# MAAV_roomba.net
KiCad netlist of a schematic drawn in EAGLE
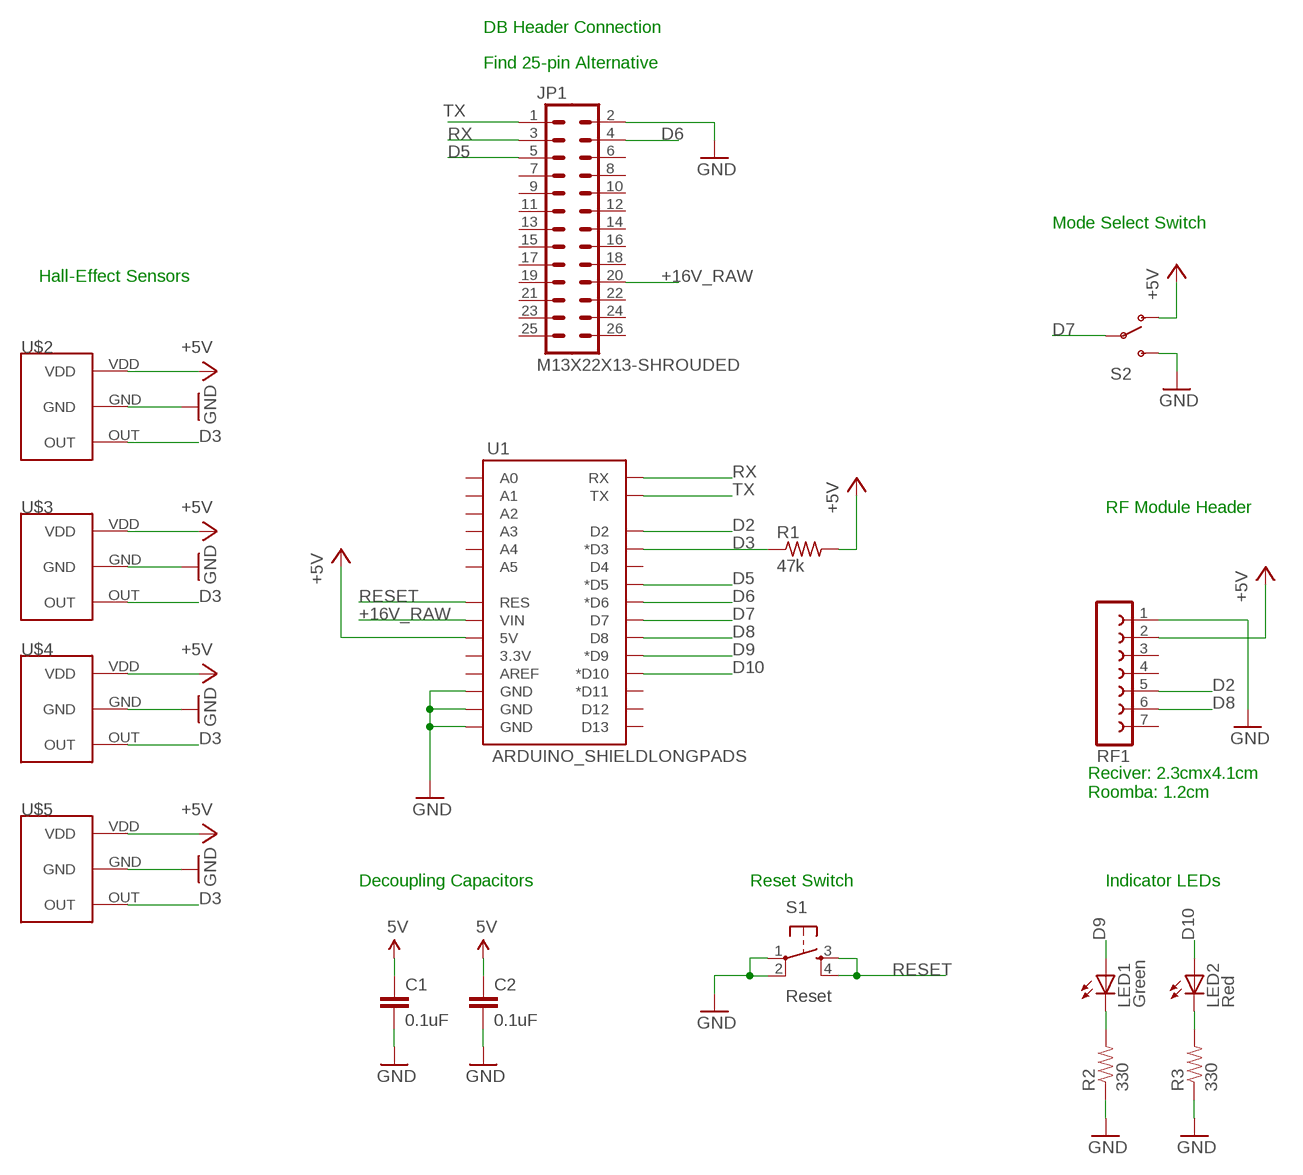
[diagram p0: schematic, sheet 1]

(export (version "E")
  (design (tool "Eeschema 10.0.6"))
  (components
    (comp (ref "C1")
      (value "0.1uF")
      (footprint "eagle-import:CAP-PTH-SMALL2")
      (libsource (lib "eagle-import") (part "CAPPTH2"))
    )
    (comp (ref "C2")
      (value "0.1uF")
      (footprint "eagle-import:CAP-PTH-SMALL2")
      (libsource (lib "eagle-import") (part "CAPPTH2"))
    )
    (comp (ref "JP1")
      (value "M13X22X13-SHROUDED")
      (footprint "eagle-import:2X25-SHROUDED")
      (libsource (lib "eagle-import") (part "M13X22X13-SHROUDED"))
    )
    (comp (ref "LED1")
      (value "Green")
      (footprint "eagle-import:LED5MM")
      (libsource (lib "eagle-import") (part "LED5MM"))
    )
    (comp (ref "LED2")
      (value "Red")
      (footprint "eagle-import:LED5MM")
      (libsource (lib "eagle-import") (part "LED5MM"))
    )
    (comp (ref "R1")
      (value "47k")
      (footprint "eagle-import:0309_10")
      (libsource (lib "eagle-import") (part "R-US_0309/10"))
    )
    (comp (ref "R2")
      (value "330")
      (footprint "eagle-import:AXIAL-0.4")
      (libsource (lib "eagle-import") (part "RESISTORPTH-1/4W"))
    )
    (comp (ref "R3")
      (value "330")
      (footprint "eagle-import:AXIAL-0.4")
      (libsource (lib "eagle-import") (part "RESISTORPTH-1/4W"))
    )
    (comp (ref "RF1")
      (value "FE07W")
      (footprint "eagle-import:FE07W")
      (libsource (lib "eagle-import") (part "FE07W"))
    )
    (comp (ref "S1")
      (value "Reset")
      (footprint "eagle-import:TACTILE-PTH")
      (libsource (lib "eagle-import") (part "TAC_SWITCHPTH"))
    )
    (comp (ref "S2")
      (value "SWITCH-SPDTPTH")
      (footprint "eagle-import:SWITCH-SPDT")
      (libsource (lib "eagle-import") (part "SWITCH-SPDTPTH"))
    )
    (comp (ref "U$2")
      (value "HALL_EFFECT")
      (footprint "eagle-import:HALL_EFFECT")
      (libsource (lib "eagle-import") (part "HALL_EFFECT"))
    )
    (comp (ref "U$3")
      (value "HALL_EFFECT")
      (footprint "eagle-import:HALL_EFFECT")
      (libsource (lib "eagle-import") (part "HALL_EFFECT"))
    )
    (comp (ref "U$4")
      (value "HALL_EFFECT")
      (footprint "eagle-import:HALL_EFFECT")
      (libsource (lib "eagle-import") (part "HALL_EFFECT"))
    )
    (comp (ref "U$5")
      (value "HALL_EFFECT")
      (footprint "eagle-import:HALL_EFFECT")
      (libsource (lib "eagle-import") (part "HALL_EFFECT"))
    )
    (comp (ref "U1")
      (value "ARDUINO_SHIELDLONGPADS")
      (footprint "eagle-import:DUEMILANOVE_SHIELD_LONGPADS")
      (libsource (lib "eagle-import") (part "ARDUINO_SHIELDLONGPADS"))
    )
  )
  (nets
    (net (code "1") (name "+5V") (class "Default")
      (node (ref "C1") (pin "1") (pinfunction "1_1") (pintype "passive"))
      (node (ref "C2") (pin "1") (pinfunction "1_1") (pintype "passive"))
      (node (ref "R1") (pin "2") (pinfunction "2_2") (pintype "passive"))
      (node (ref "RF1") (pin "2") (pinfunction "2_2") (pintype "passive"))
      (node (ref "S2") (pin "1") (pinfunction "O_1") (pintype "passive"))
      (node (ref "U$2") (pin "VDD") (pinfunction "VDD_VDD") (pintype "bidirectional"))
      (node (ref "U$3") (pin "VDD") (pinfunction "VDD_VDD") (pintype "bidirectional"))
      (node (ref "U$4") (pin "VDD") (pinfunction "VDD_VDD") (pintype "bidirectional"))
      (node (ref "U$5") (pin "VDD") (pinfunction "VDD_VDD") (pintype "bidirectional"))
      (node (ref "U1") (pin "5V") (pinfunction "5V_5V") (pintype "bidirectional"))
    )
    (net (code "2") (name "/+16V_RAW") (class "Default")
      (node (ref "JP1") (pin "20") (pinfunction "20_20") (pintype "passive"))
      (node (ref "U1") (pin "VIN") (pinfunction "VIN_VIN") (pintype "bidirectional"))
    )
    (net (code "3") (name "/D2") (class "Default")
      (node (ref "RF1") (pin "5") (pinfunction "5_5") (pintype "passive"))
      (node (ref "U1") (pin "D2") (pinfunction "D2_D2") (pintype "bidirectional"))
    )
    (net (code "4") (name "/D3") (class "Default")
      (node (ref "R1") (pin "1") (pinfunction "1_1") (pintype "passive"))
      (node (ref "U$2") (pin "OUT") (pinfunction "OUT_OUT") (pintype "bidirectional"))
      (node (ref "U$3") (pin "OUT") (pinfunction "OUT_OUT") (pintype "bidirectional"))
      (node (ref "U$4") (pin "OUT") (pinfunction "OUT_OUT") (pintype "bidirectional"))
      (node (ref "U$5") (pin "OUT") (pinfunction "OUT_OUT") (pintype "bidirectional"))
      (node (ref "U1") (pin "D3") (pinfunction "*D3_D3") (pintype "bidirectional"))
    )
    (net (code "5") (name "/D5") (class "Default")
      (node (ref "JP1") (pin "5") (pinfunction "5_5") (pintype "passive"))
      (node (ref "U1") (pin "D5") (pinfunction "*D5_D5") (pintype "bidirectional"))
    )
    (net (code "6") (name "/D6") (class "Default")
      (node (ref "JP1") (pin "4") (pinfunction "4_4") (pintype "passive"))
      (node (ref "U1") (pin "D6") (pinfunction "*D6_D6") (pintype "bidirectional"))
    )
    (net (code "7") (name "/D7") (class "Default")
      (node (ref "S2") (pin "2") (pinfunction "P_2") (pintype "passive"))
      (node (ref "U1") (pin "D7") (pinfunction "D7_D7") (pintype "bidirectional"))
    )
    (net (code "8") (name "/D8") (class "Default")
      (node (ref "RF1") (pin "6") (pinfunction "6_6") (pintype "passive"))
      (node (ref "U1") (pin "D8") (pinfunction "D8_D8") (pintype "bidirectional"))
    )
    (net (code "9") (name "/D9") (class "Default")
      (node (ref "LED1") (pin "A") (pinfunction "A_A") (pintype "passive"))
      (node (ref "U1") (pin "D9") (pinfunction "*D9_D9") (pintype "bidirectional"))
    )
    (net (code "10") (name "/D10") (class "Default")
      (node (ref "LED2") (pin "A") (pinfunction "A_A") (pintype "passive"))
      (node (ref "U1") (pin "D10") (pinfunction "*D10_D10") (pintype "bidirectional"))
    )
    (net (code "11") (name "/RESET") (class "Default")
      (node (ref "S1") (pin "3") (pinfunction "3_3") (pintype "passive"))
      (node (ref "S1") (pin "4") (pinfunction "4_4") (pintype "passive"))
      (node (ref "U1") (pin "RES") (pinfunction "RES_RES") (pintype "bidirectional"))
    )
    (net (code "12") (name "/RX") (class "Default")
      (node (ref "JP1") (pin "3") (pinfunction "3_3") (pintype "passive"))
      (node (ref "U1") (pin "RX") (pinfunction "RX_RX") (pintype "bidirectional"))
    )
    (net (code "13") (name "/TX") (class "Default")
      (node (ref "JP1") (pin "1") (pinfunction "1_1") (pintype "passive"))
      (node (ref "U1") (pin "TX") (pinfunction "TX_TX") (pintype "bidirectional"))
    )
    (net (code "14") (name "GND") (class "Default")
      (node (ref "C1") (pin "2") (pinfunction "2_2") (pintype "passive"))
      (node (ref "C2") (pin "2") (pinfunction "2_2") (pintype "passive"))
      (node (ref "JP1") (pin "2") (pinfunction "2_2") (pintype "passive"))
      (node (ref "R2") (pin "P$1") (pinfunction "1_P$1") (pintype "passive"))
      (node (ref "R3") (pin "P$1") (pinfunction "1_P$1") (pintype "passive"))
      (node (ref "RF1") (pin "1") (pinfunction "1_1") (pintype "passive"))
      (node (ref "S1") (pin "1") (pinfunction "1_1") (pintype "passive"))
      (node (ref "S1") (pin "2") (pinfunction "2_2") (pintype "passive"))
      (node (ref "S2") (pin "3") (pinfunction "S_3") (pintype "passive"))
      (node (ref "U$2") (pin "GND") (pinfunction "GND_GND") (pintype "bidirectional"))
      (node (ref "U$3") (pin "GND") (pinfunction "GND_GND") (pintype "bidirectional"))
      (node (ref "U$4") (pin "GND") (pinfunction "GND_GND") (pintype "bidirectional"))
      (node (ref "U$5") (pin "GND") (pinfunction "GND_GND") (pintype "bidirectional"))
      (node (ref "U1") (pin "GND@0") (pinfunction "GND_GND@0") (pintype "bidirectional"))
      (node (ref "U1") (pin "GND@1") (pinfunction "GND_GND@1") (pintype "bidirectional"))
      (node (ref "U1") (pin "GND@2") (pinfunction "GND_GND@2") (pintype "bidirectional"))
    )
    (net (code "15") (name "Net-(LED1-C)") (class "Default")
      (node (ref "LED1") (pin "K") (pinfunction "C_K") (pintype "passive"))
      (node (ref "R2") (pin "P$2") (pinfunction "2_P$2") (pintype "passive"))
    )
    (net (code "16") (name "Net-(LED2-C)") (class "Default")
      (node (ref "LED2") (pin "K") (pinfunction "C_K") (pintype "passive"))
      (node (ref "R3") (pin "P$2") (pinfunction "2_P$2") (pintype "passive"))
    )
    (net (code "17") (name "unconnected-(JP1-Pad6)") (class "Default")
      (node (ref "JP1") (pin "6") (pinfunction "6_6") (pintype "passive"))
    )
    (net (code "18") (name "unconnected-(JP1-Pad7)") (class "Default")
      (node (ref "JP1") (pin "7") (pinfunction "7_7") (pintype "passive"))
    )
    (net (code "19") (name "unconnected-(JP1-Pad8)") (class "Default")
      (node (ref "JP1") (pin "8") (pinfunction "8_8") (pintype "passive"))
    )
    (net (code "20") (name "unconnected-(JP1-Pad9)") (class "Default")
      (node (ref "JP1") (pin "9") (pinfunction "9_9") (pintype "passive"))
    )
    (net (code "21") (name "unconnected-(JP1-Pad10)") (class "Default")
      (node (ref "JP1") (pin "10") (pinfunction "10_10") (pintype "passive"))
    )
    (net (code "22") (name "unconnected-(JP1-Pad11)") (class "Default")
      (node (ref "JP1") (pin "11") (pinfunction "11_11") (pintype "passive"))
    )
    (net (code "23") (name "unconnected-(JP1-Pad12)") (class "Default")
      (node (ref "JP1") (pin "12") (pinfunction "12_12") (pintype "passive"))
    )
    (net (code "24") (name "unconnected-(JP1-Pad13)") (class "Default")
      (node (ref "JP1") (pin "13") (pinfunction "13_13") (pintype "passive"))
    )
    (net (code "25") (name "unconnected-(JP1-Pad14)") (class "Default")
      (node (ref "JP1") (pin "14") (pinfunction "14_14") (pintype "passive"))
    )
    (net (code "26") (name "unconnected-(JP1-Pad15)") (class "Default")
      (node (ref "JP1") (pin "15") (pinfunction "15_15") (pintype "passive"))
    )
    (net (code "27") (name "unconnected-(JP1-Pad16)") (class "Default")
      (node (ref "JP1") (pin "16") (pinfunction "16_16") (pintype "passive"))
    )
    (net (code "28") (name "unconnected-(JP1-Pad17)") (class "Default")
      (node (ref "JP1") (pin "17") (pinfunction "17_17") (pintype "passive"))
    )
    (net (code "29") (name "unconnected-(JP1-Pad18)") (class "Default")
      (node (ref "JP1") (pin "18") (pinfunction "18_18") (pintype "passive"))
    )
    (net (code "30") (name "unconnected-(JP1-Pad19)") (class "Default")
      (node (ref "JP1") (pin "19") (pinfunction "19_19") (pintype "passive"))
    )
    (net (code "31") (name "unconnected-(JP1-Pad21)") (class "Default")
      (node (ref "JP1") (pin "21") (pinfunction "21_21") (pintype "passive"))
    )
    (net (code "32") (name "unconnected-(JP1-Pad22)") (class "Default")
      (node (ref "JP1") (pin "22") (pinfunction "22_22") (pintype "passive"))
    )
    (net (code "33") (name "unconnected-(JP1-Pad23)") (class "Default")
      (node (ref "JP1") (pin "23") (pinfunction "23_23") (pintype "passive"))
    )
    (net (code "34") (name "unconnected-(JP1-Pad24)") (class "Default")
      (node (ref "JP1") (pin "24") (pinfunction "24_24") (pintype "passive"))
    )
    (net (code "35") (name "unconnected-(JP1-Pad25)") (class "Default")
      (node (ref "JP1") (pin "25") (pinfunction "25_25") (pintype "passive"))
    )
    (net (code "36") (name "unconnected-(JP1-Pad26)") (class "Default")
      (node (ref "JP1") (pin "26") (pinfunction "26_26") (pintype "passive"))
    )
    (net (code "37") (name "unconnected-(RF1-Pad3)") (class "Default")
      (node (ref "RF1") (pin "3") (pinfunction "3_3") (pintype "passive"))
    )
    (net (code "38") (name "unconnected-(RF1-Pad4)") (class "Default")
      (node (ref "RF1") (pin "4") (pinfunction "4_4") (pintype "passive"))
    )
    (net (code "39") (name "unconnected-(RF1-Pad7)") (class "Default")
      (node (ref "RF1") (pin "7") (pinfunction "7_7") (pintype "passive"))
    )
    (net (code "40") (name "unconnected-(U1-*D11-PadD11)") (class "Default")
      (node (ref "U1") (pin "D11") (pinfunction "*D11_D11") (pintype "bidirectional"))
    )
    (net (code "41") (name "unconnected-(U1-Pad3.3V)") (class "Default")
      (node (ref "U1") (pin "3.3V") (pinfunction "3.3V_3.3V") (pintype "bidirectional"))
    )
    (net (code "42") (name "unconnected-(U1-PadA0)") (class "Default")
      (node (ref "U1") (pin "A0") (pinfunction "A0_A0") (pintype "bidirectional"))
    )
    (net (code "43") (name "unconnected-(U1-PadA1)") (class "Default")
      (node (ref "U1") (pin "A1") (pinfunction "A1_A1") (pintype "bidirectional"))
    )
    (net (code "44") (name "unconnected-(U1-PadA2)") (class "Default")
      (node (ref "U1") (pin "A2") (pinfunction "A2_A2") (pintype "bidirectional"))
    )
    (net (code "45") (name "unconnected-(U1-PadA3)") (class "Default")
      (node (ref "U1") (pin "A3") (pinfunction "A3_A3") (pintype "bidirectional"))
    )
    (net (code "46") (name "unconnected-(U1-PadA4)") (class "Default")
      (node (ref "U1") (pin "A4") (pinfunction "A4_A4") (pintype "bidirectional"))
    )
    (net (code "47") (name "unconnected-(U1-PadA5)") (class "Default")
      (node (ref "U1") (pin "A5") (pinfunction "A5_A5") (pintype "bidirectional"))
    )
    (net (code "48") (name "unconnected-(U1-PadAREF)") (class "Default")
      (node (ref "U1") (pin "AREF") (pinfunction "AREF_AREF") (pintype "bidirectional"))
    )
    (net (code "49") (name "unconnected-(U1-PadD4)") (class "Default")
      (node (ref "U1") (pin "D4") (pinfunction "D4_D4") (pintype "bidirectional"))
    )
    (net (code "50") (name "unconnected-(U1-PadD12)") (class "Default")
      (node (ref "U1") (pin "D12") (pinfunction "D12_D12") (pintype "bidirectional"))
    )
    (net (code "51") (name "unconnected-(U1-PadD13)") (class "Default")
      (node (ref "U1") (pin "D13") (pinfunction "D13_D13") (pintype "bidirectional"))
    )
  )
)
